# 0124-logic-level-shifter.net
KiCad netlist of a schematic drawn in EAGLE
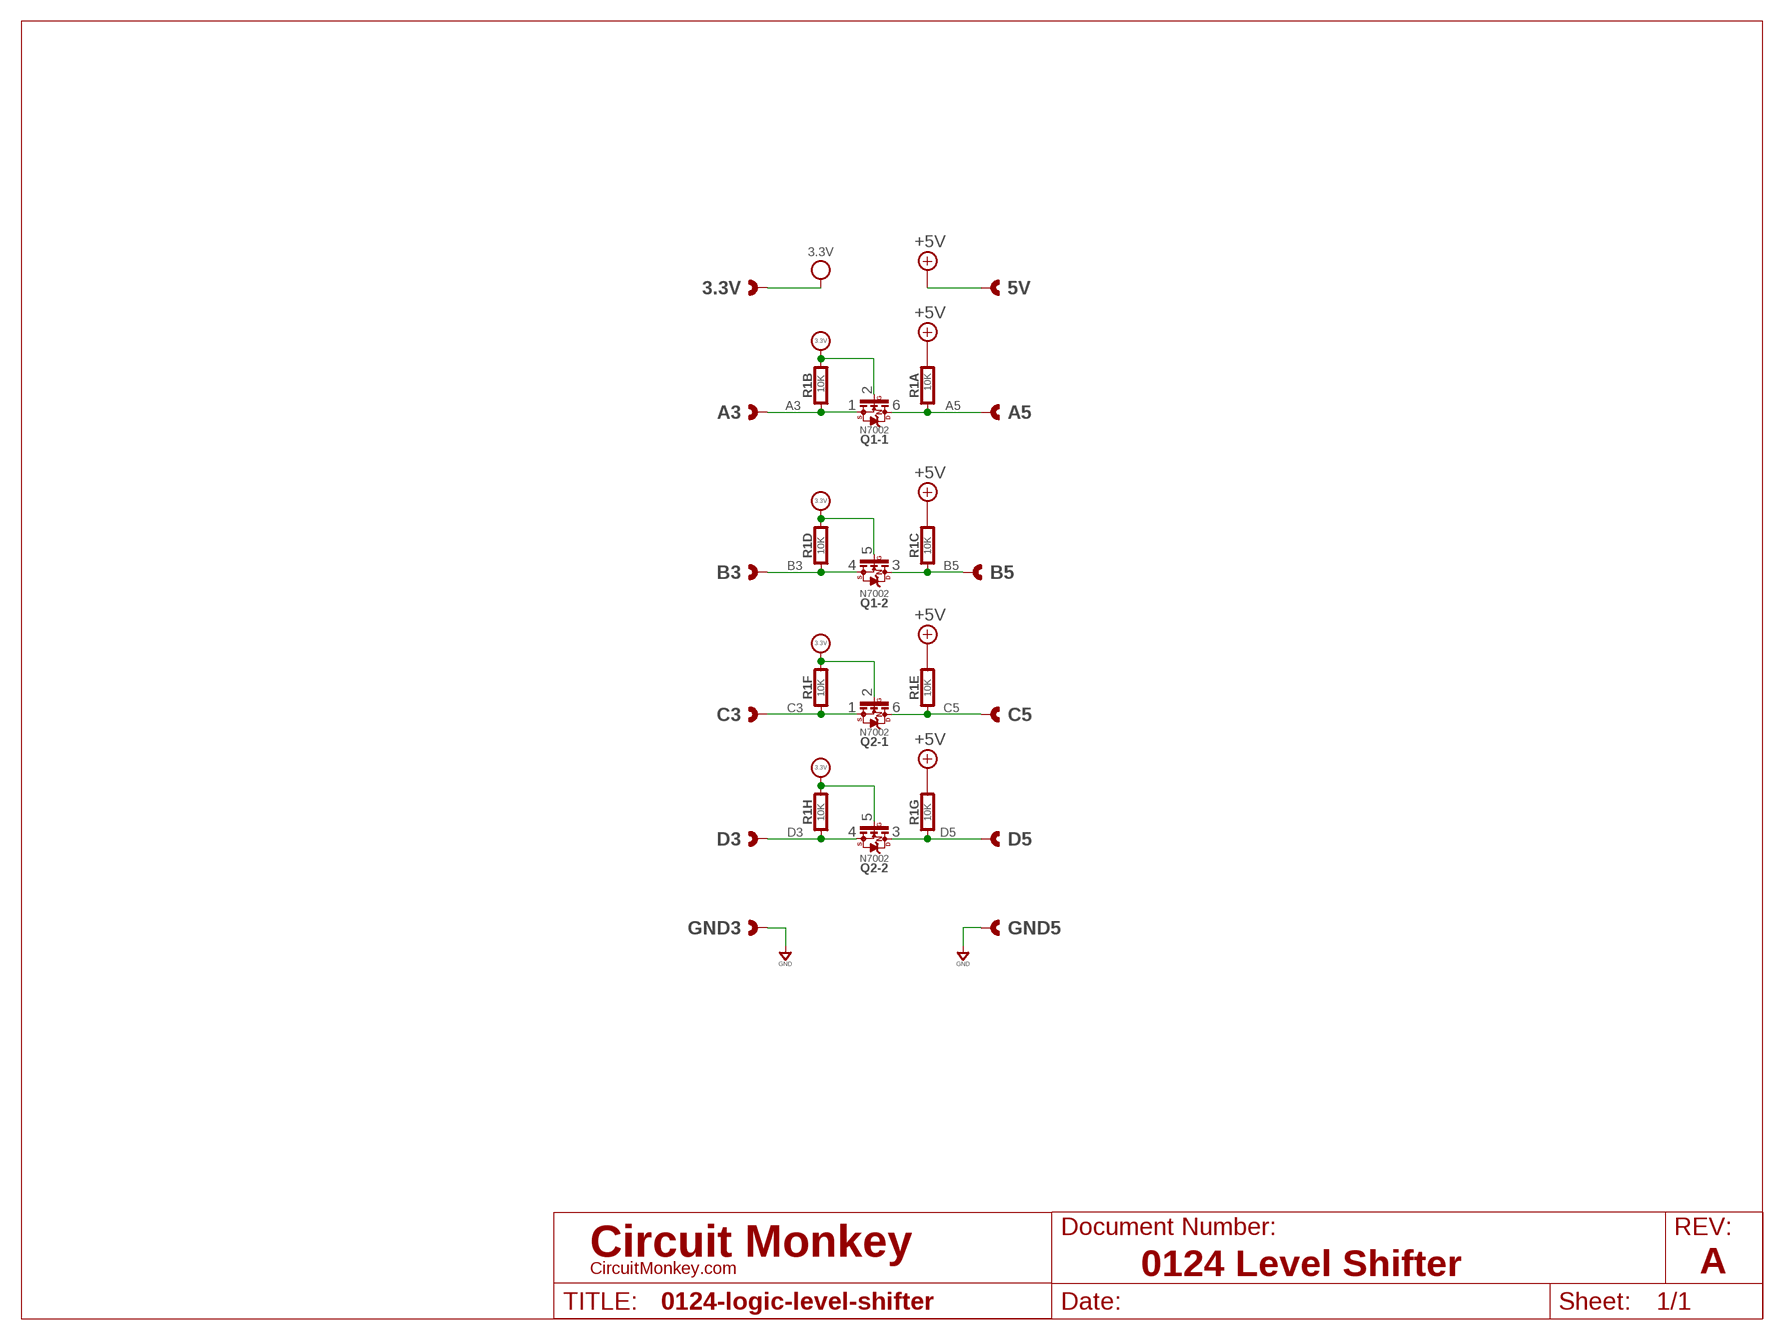
[diagram p0: schematic, sheet 1]

(export (version "E")
  (design (tool "Eeschema 10.0.6"))
  (components
    (comp (ref "3.3V")
      (value "CAST-01X12.00MM")
      (footprint "eagle-import:CAST01-2.00MM")
      (libsource (lib "eagle-import") (part "CAST-01X12.00MM"))
    )
    (comp (ref "5V")
      (value "CAST-01X12.00MM")
      (footprint "eagle-import:CAST01-2.00MM")
      (libsource (lib "eagle-import") (part "CAST-01X12.00MM"))
    )
    (comp (ref "A3")
      (value "CAST-01X12.00MM")
      (footprint "eagle-import:CAST01-2.00MM")
      (libsource (lib "eagle-import") (part "CAST-01X12.00MM"))
    )
    (comp (ref "A5")
      (value "CAST-01X12.00MM")
      (footprint "eagle-import:CAST01-2.00MM")
      (libsource (lib "eagle-import") (part "CAST-01X12.00MM"))
    )
    (comp (ref "B3")
      (value "CAST-01X12.00MM")
      (footprint "eagle-import:CAST01-2.00MM")
      (libsource (lib "eagle-import") (part "CAST-01X12.00MM"))
    )
    (comp (ref "B5")
      (value "CAST-01X12.00MM")
      (footprint "eagle-import:CAST01-2.00MM")
      (libsource (lib "eagle-import") (part "CAST-01X12.00MM"))
    )
    (comp (ref "C3")
      (value "CAST-01X12.00MM")
      (footprint "eagle-import:CAST01-2.00MM")
      (libsource (lib "eagle-import") (part "CAST-01X12.00MM"))
    )
    (comp (ref "C5")
      (value "CAST-01X12.00MM")
      (footprint "eagle-import:CAST01-2.00MM")
      (libsource (lib "eagle-import") (part "CAST-01X12.00MM"))
    )
    (comp (ref "D3")
      (value "CAST-01X12.00MM")
      (footprint "eagle-import:CAST01-2.00MM")
      (libsource (lib "eagle-import") (part "CAST-01X12.00MM"))
    )
    (comp (ref "D5")
      (value "CAST-01X12.00MM")
      (footprint "eagle-import:CAST01-2.00MM")
      (libsource (lib "eagle-import") (part "CAST-01X12.00MM"))
    )
    (comp (ref "GND3")
      (value "CAST-01X12.00MM")
      (footprint "eagle-import:CAST01-2.00MM")
      (libsource (lib "eagle-import") (part "CAST-01X12.00MM"))
    )
    (comp (ref "GND5")
      (value "CAST-01X12.00MM")
      (footprint "eagle-import:CAST01-2.00MM")
      (libsource (lib "eagle-import") (part "CAST-01X12.00MM"))
    )
    (comp (ref "Q1")
      (value "N7002")
      (footprint "eagle-import:SOT-563")
      (fields (field (name "MFR") "Toshiba") (field (name "MPN") "SSM6N7002BFE"))
      (libsource (lib "eagle-import") (part "N-FET_DUAL7002"))
    )
    (comp (ref "Q2")
      (value "N7002")
      (footprint "eagle-import:SOT-563")
      (fields (field (name "MFR") "Toshiba") (field (name "MPN") "SSM6N7002BFE"))
      (libsource (lib "eagle-import") (part "N-FET_DUAL7002"))
    )
    (comp (ref "R1")
      (value "10K")
      (footprint "eagle-import:RESNET_0402_X8")
      (fields (field (name "MFR") "Panasonic'") (field (name "MPN") "EXB2HVxxx"))
      (libsource (lib "eagle-import") (part "RESNET_0402_INDIV_X8PAN"))
    )
  )
  (nets
    (net (code "1") (name "+5V") (class "Default")
      (node (ref "5V") (pin "1") (pinfunction "1_1") (pintype "bidirectional"))
      (node (ref "5V") (pin "P$1") (pinfunction "1_P$1") (pintype "bidirectional"))
      (node (ref "5V") (pin "P$2") (pinfunction "1_P$2") (pintype "bidirectional"))
      (node (ref "R1") (pin "10") (pinfunction "2_10") (pintype "passive"))
      (node (ref "R1") (pin "12") (pinfunction "2_12") (pintype "passive"))
      (node (ref "R1") (pin "14") (pinfunction "2_14") (pintype "passive"))
      (node (ref "R1") (pin "16") (pinfunction "2_16") (pintype "passive"))
    )
    (net (code "2") (name "/A3") (class "Default")
      (node (ref "A3") (pin "1") (pinfunction "1_1") (pintype "bidirectional"))
      (node (ref "A3") (pin "P$1") (pinfunction "1_P$1") (pintype "bidirectional"))
      (node (ref "A3") (pin "P$2") (pinfunction "1_P$2") (pintype "bidirectional"))
      (node (ref "Q1") (pin "1") (pinfunction "S_1") (pintype "bidirectional"))
      (node (ref "R1") (pin "2") (pinfunction "1_2") (pintype "passive"))
    )
    (net (code "3") (name "/A5") (class "Default")
      (node (ref "A5") (pin "1") (pinfunction "1_1") (pintype "bidirectional"))
      (node (ref "A5") (pin "P$1") (pinfunction "1_P$1") (pintype "bidirectional"))
      (node (ref "A5") (pin "P$2") (pinfunction "1_P$2") (pintype "bidirectional"))
      (node (ref "Q1") (pin "6") (pinfunction "D_6") (pintype "bidirectional"))
      (node (ref "R1") (pin "1") (pinfunction "1_1") (pintype "passive"))
    )
    (net (code "4") (name "/B3") (class "Default")
      (node (ref "B3") (pin "1") (pinfunction "1_1") (pintype "bidirectional"))
      (node (ref "B3") (pin "P$1") (pinfunction "1_P$1") (pintype "bidirectional"))
      (node (ref "B3") (pin "P$2") (pinfunction "1_P$2") (pintype "bidirectional"))
      (node (ref "Q1") (pin "4") (pinfunction "S_4") (pintype "bidirectional"))
      (node (ref "R1") (pin "4") (pinfunction "1_4") (pintype "passive"))
    )
    (net (code "5") (name "/B5") (class "Default")
      (node (ref "B5") (pin "1") (pinfunction "1_1") (pintype "bidirectional"))
      (node (ref "B5") (pin "P$1") (pinfunction "1_P$1") (pintype "bidirectional"))
      (node (ref "B5") (pin "P$2") (pinfunction "1_P$2") (pintype "bidirectional"))
      (node (ref "Q1") (pin "3") (pinfunction "D_3") (pintype "bidirectional"))
      (node (ref "R1") (pin "3") (pinfunction "1_3") (pintype "passive"))
    )
    (net (code "6") (name "/C3") (class "Default")
      (node (ref "C3") (pin "1") (pinfunction "1_1") (pintype "bidirectional"))
      (node (ref "C3") (pin "P$1") (pinfunction "1_P$1") (pintype "bidirectional"))
      (node (ref "C3") (pin "P$2") (pinfunction "1_P$2") (pintype "bidirectional"))
      (node (ref "Q2") (pin "1") (pinfunction "S_1") (pintype "bidirectional"))
      (node (ref "R1") (pin "6") (pinfunction "1_6") (pintype "passive"))
    )
    (net (code "7") (name "/C5") (class "Default")
      (node (ref "C5") (pin "1") (pinfunction "1_1") (pintype "bidirectional"))
      (node (ref "C5") (pin "P$1") (pinfunction "1_P$1") (pintype "bidirectional"))
      (node (ref "C5") (pin "P$2") (pinfunction "1_P$2") (pintype "bidirectional"))
      (node (ref "Q2") (pin "6") (pinfunction "D_6") (pintype "bidirectional"))
      (node (ref "R1") (pin "5") (pinfunction "1_5") (pintype "passive"))
    )
    (net (code "8") (name "/D3") (class "Default")
      (node (ref "D3") (pin "1") (pinfunction "1_1") (pintype "bidirectional"))
      (node (ref "D3") (pin "P$1") (pinfunction "1_P$1") (pintype "bidirectional"))
      (node (ref "D3") (pin "P$2") (pinfunction "1_P$2") (pintype "bidirectional"))
      (node (ref "Q2") (pin "4") (pinfunction "S_4") (pintype "bidirectional"))
      (node (ref "R1") (pin "8") (pinfunction "1_8") (pintype "passive"))
    )
    (net (code "9") (name "/D5") (class "Default")
      (node (ref "D5") (pin "1") (pinfunction "1_1") (pintype "bidirectional"))
      (node (ref "D5") (pin "P$1") (pinfunction "1_P$1") (pintype "bidirectional"))
      (node (ref "D5") (pin "P$2") (pinfunction "1_P$2") (pintype "bidirectional"))
      (node (ref "Q2") (pin "3") (pinfunction "D_3") (pintype "bidirectional"))
      (node (ref "R1") (pin "7") (pinfunction "1_7") (pintype "passive"))
    )
    (net (code "10") (name "3.3V") (class "Default")
      (node (ref "3.3V") (pin "1") (pinfunction "1_1") (pintype "bidirectional"))
      (node (ref "3.3V") (pin "P$1") (pinfunction "1_P$1") (pintype "bidirectional"))
      (node (ref "3.3V") (pin "P$2") (pinfunction "1_P$2") (pintype "bidirectional"))
      (node (ref "Q1") (pin "2") (pinfunction "G_2") (pintype "bidirectional"))
      (node (ref "Q1") (pin "5") (pinfunction "G_5") (pintype "bidirectional"))
      (node (ref "Q2") (pin "2") (pinfunction "G_2") (pintype "bidirectional"))
      (node (ref "Q2") (pin "5") (pinfunction "G_5") (pintype "bidirectional"))
      (node (ref "R1") (pin "11") (pinfunction "2_11") (pintype "passive"))
      (node (ref "R1") (pin "13") (pinfunction "2_13") (pintype "passive"))
      (node (ref "R1") (pin "15") (pinfunction "2_15") (pintype "passive"))
      (node (ref "R1") (pin "9") (pinfunction "2_9") (pintype "passive"))
    )
    (net (code "11") (name "GND") (class "Default")
      (node (ref "GND3") (pin "1") (pinfunction "1_1") (pintype "bidirectional"))
      (node (ref "GND3") (pin "P$1") (pinfunction "1_P$1") (pintype "bidirectional"))
      (node (ref "GND3") (pin "P$2") (pinfunction "1_P$2") (pintype "bidirectional"))
      (node (ref "GND5") (pin "1") (pinfunction "1_1") (pintype "bidirectional"))
      (node (ref "GND5") (pin "P$1") (pinfunction "1_P$1") (pintype "bidirectional"))
      (node (ref "GND5") (pin "P$2") (pinfunction "1_P$2") (pintype "bidirectional"))
    )
  )
)
